# Sensors.net
KiCad netlist of a schematic drawn in Altium Designer
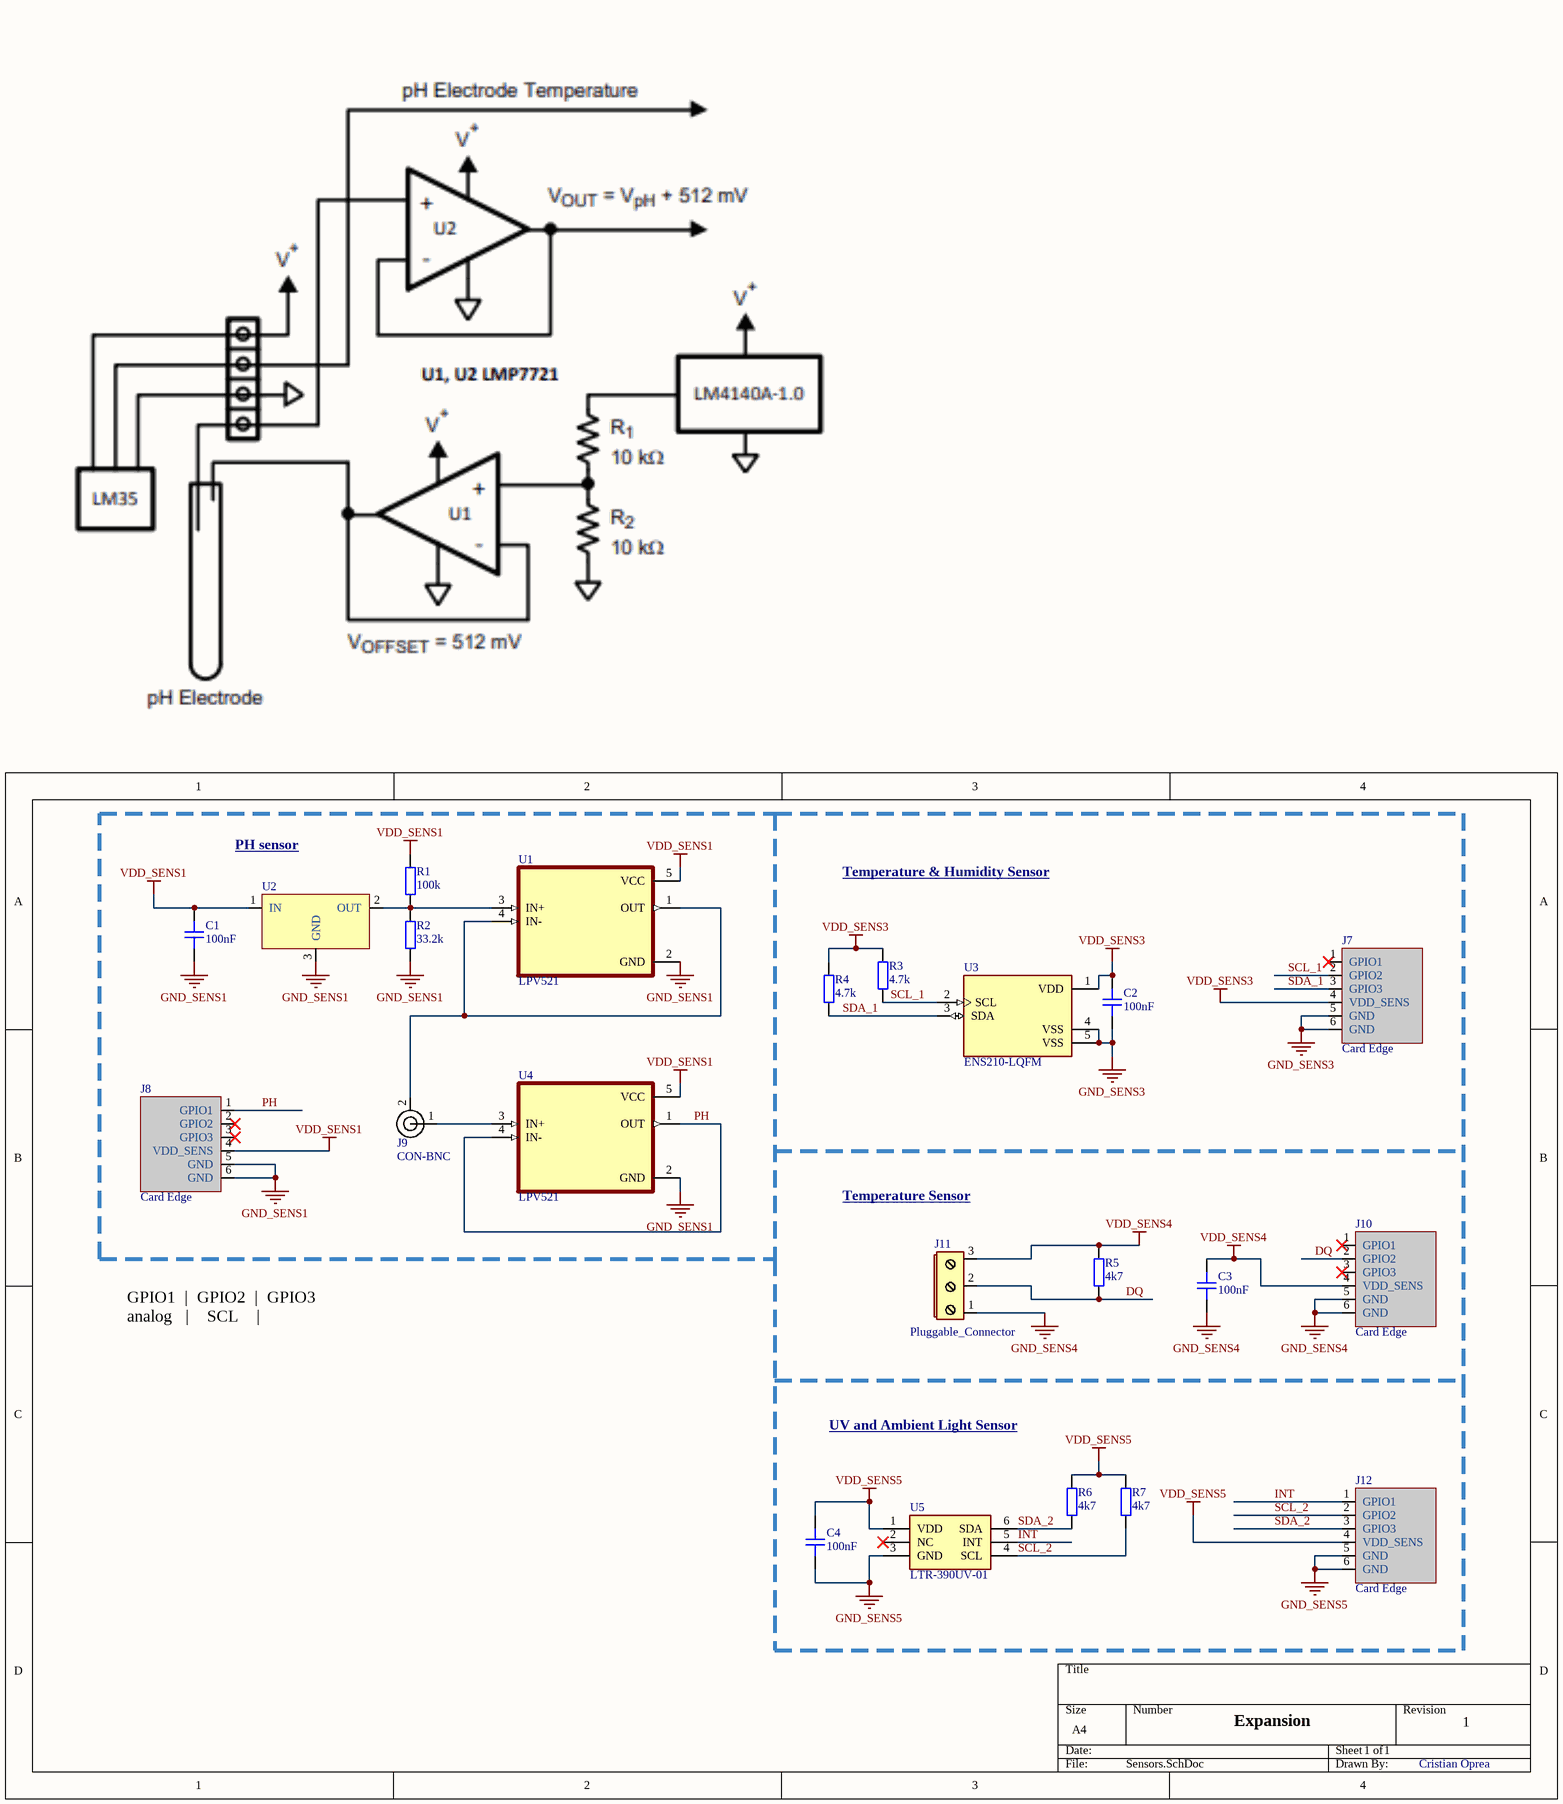
[diagram p0: Sensors.SchDoc]

(export (version "E")
  (design (tool "Eeschema 10.0.6"))
  (components
    (comp (ref "C1")
      (value "100nF")
      (footprint "C0603")
      (description "Capacitor SMD 0603")
      (libsource (lib "Schlib1") (part "CAP_0603"))
    )
    (comp (ref "C2")
      (value "100nF")
      (footprint "C0603")
      (description "Capacitor SMD 0603")
      (libsource (lib "Schlib1") (part "CAP_0603"))
    )
    (comp (ref "C3")
      (value "100nF")
      (footprint "C0603")
      (description "Capacitor SMD 0603")
      (libsource (lib "Schlib1") (part "CAP_0603"))
    )
    (comp (ref "C4")
      (value "100nF")
      (footprint "C0603")
      (description "Capacitor SMD 0603")
      (libsource (lib "Schlib1") (part "CAP_0603"))
    )
    (comp (ref "J7")
      (value "Card Edge")
      (footprint "Card Edge")
      (description "Card Edge pads for 2.54 mm pitch edge connector")
      (libsource (lib "") (part "Card Edge_1"))
    )
    (comp (ref "J8")
      (value "Card Edge")
      (footprint "Card Edge")
      (description "Card Edge pads for 2.54 mm pitch edge connector")
      (libsource (lib "Schlib1") (part "Card Edge"))
    )
    (comp (ref "J9")
      (value "CON-BNC")
      (footprint "CON_BNC_MOLEX_0731375003")
      (description "RF Connector BNC Female 50 Ohms PCB TH Mount")
      (fields
        (field (name "MANUFACTURER") "RF Solutions")
        (field (name "MANUFACTURER PART NUMBER") "CON-SMA-EDGE-S")
      )
      (libsource (lib "Schlib1") (part "CON-BNC"))
    )
    (comp (ref "J10")
      (value "Card Edge")
      (footprint "Card Edge")
      (description "Card Edge pads for 2.54 mm pitch edge connector")
      (libsource (lib "") (part "Card Edge_1"))
    )
    (comp (ref "J11")
      (value "Pluggable_Connector")
      (footprint "5mm_screw_terminal_3_pos")
      (description "Screw terminal or plug terminal")
      (libsource (lib "Schlib1") (part "Pluggable_Connector"))
    )
    (comp (ref "J12")
      (value "Card Edge")
      (footprint "Card Edge")
      (description "Card Edge pads for 2.54 mm pitch edge connector")
      (libsource (lib "") (part "Card Edge_1"))
    )
    (comp (ref "R1")
      (value "100k")
      (footprint "R0603")
      (description "Resistor SMD 0603")
      (libsource (lib "Schlib1") (part "RES_0603"))
    )
    (comp (ref "R2")
      (value "33.2k")
      (footprint "R0603")
      (description "Resistor SMD 0603")
      (libsource (lib "Schlib1") (part "RES_0603"))
    )
    (comp (ref "R3")
      (value "4.7k")
      (footprint "R0603")
      (description "Resistor SMD 0603")
      (libsource (lib "Schlib1") (part "RES_0603"))
    )
    (comp (ref "R4")
      (value "4.7k")
      (footprint "R0603")
      (description "Resistor SMD 0603")
      (libsource (lib "Schlib1") (part "RES_0603"))
    )
    (comp (ref "R5")
      (value "4k7")
      (footprint "R0603")
      (description "Resistor SMD 0805")
      (libsource (lib "Schlib1") (part "RES_0805"))
    )
    (comp (ref "R6")
      (value "4k7")
      (footprint "R0603")
      (description "Resistor SMD 0805")
      (libsource (lib "Schlib1") (part "RES_0805"))
    )
    (comp (ref "R7")
      (value "4k7")
      (footprint "R0603")
      (description "Resistor SMD 0805")
      (libsource (lib "Schlib1") (part "RES_0805"))
    )
    (comp (ref "U1")
      (value "LPV521")
      (footprint "SOT65P210X110-5N")
      (fields (field (name "MP") "MAX4466EXK"))
      (libsource (lib "Schlib1") (part "LPV521"))
    )
    (comp (ref "U2")
      (value "ADR5040BKSZ-REEL7")
      (footprint "SOT23-3")
      (description "Voltage References 2.048 Low-Cost, Micropower, Low-Dropout, High-Output-Current, SOT23")
      (fields
        (field (name "MANUFACTURER") "Maxim Integrated")
        (field (name "MANUFACTURER PART NUMBER") "MAX6101EUR+T")
      )
      (libsource (lib "Schlib1") (part "VREF"))
    )
    (comp (ref "U3")
      (value "ENS210-LQFM")
      (footprint "XDCR_ENS210-LQFM")
      (description "Humidity/Temperature Sensor Digital Serial (2-Wire, I2C) 4-Pin QFN EP T/R")
      (fields (field (name "MF") "ScioSense"))
      (libsource (lib "Schlib1") (part "ENS210-LQFM"))
    )
    (comp (ref "U4")
      (value "LPV521")
      (footprint "SOT65P210X110-5N")
      (fields (field (name "MP") "MAX4466EXK"))
      (libsource (lib "Schlib1") (part "LPV521"))
    )
    (comp (ref "U5")
      (value "LTR-390UV-01")
      (footprint "LTR390-UV")
      (description "SENSOR OPT ULTRAVIOLET 6PINS")
      (fields (field (name "MOUSER PART NUMBER") "859-LTR390UV01"))
      (libsource (lib "Schlib1") (part "LTR-390UV-01"))
    )
  )
  (nets
    (net (code "1") (name "/DQ") (class "Default")
      (node (ref "J10") (pin "2") (pinfunction "GPIO2_2") (pintype "passive"))
      (node (ref "J11") (pin "2") (pinfunction "2_2") (pintype "passive"))
      (node (ref "R5") (pin "1") (pinfunction "1_1") (pintype "passive"))
    )
    (net (code "2") (name "/INT") (class "Default")
      (node (ref "J12") (pin "1") (pinfunction "GPIO1_1") (pintype "passive"))
      (node (ref "U5") (pin "5") (pinfunction "INT_5") (pintype "passive"))
    )
    (net (code "3") (name "/PH") (class "Default")
      (node (ref "J8") (pin "1") (pinfunction "GPIO1_1") (pintype "passive"))
      (node (ref "U4") (pin "1") (pinfunction "OUT_1") (pintype "output"))
      (node (ref "U4") (pin "4") (pinfunction "IN-_4") (pintype "input"))
    )
    (net (code "4") (name "/SCL_1") (class "Default")
      (node (ref "J7") (pin "2") (pinfunction "GPIO2_2") (pintype "passive"))
      (node (ref "R3") (pin "1") (pinfunction "1_1") (pintype "passive"))
      (node (ref "U3") (pin "2") (pinfunction "SCL_2") (pintype "input"))
    )
    (net (code "5") (name "/SCL_2") (class "Default")
      (node (ref "J12") (pin "2") (pinfunction "GPIO2_2") (pintype "passive"))
      (node (ref "R7") (pin "1") (pinfunction "1_1") (pintype "passive"))
      (node (ref "U5") (pin "4") (pinfunction "SCL_4") (pintype "passive"))
    )
    (net (code "6") (name "/SDA_1") (class "Default")
      (node (ref "J7") (pin "3") (pinfunction "GPIO3_3") (pintype "passive"))
      (node (ref "R4") (pin "2") (pinfunction "2_2") (pintype "passive"))
      (node (ref "U3") (pin "3") (pinfunction "SDA_3") (pintype "bidirectional"))
    )
    (net (code "7") (name "/SDA_2") (class "Default")
      (node (ref "J12") (pin "3") (pinfunction "GPIO3_3") (pintype "passive"))
      (node (ref "R6") (pin "1") (pinfunction "1_1") (pintype "passive"))
      (node (ref "U5") (pin "6") (pinfunction "SDA_6") (pintype "passive"))
    )
    (net (code "8") (name "GND_SENS1") (class "Default")
      (node (ref "C1") (pin "1") (pinfunction "1_1") (pintype "passive"))
      (node (ref "J8") (pin "5") (pinfunction "GND_5") (pintype "passive"))
      (node (ref "J8") (pin "6") (pinfunction "GND_6") (pintype "passive"))
      (node (ref "R2") (pin "1") (pinfunction "1_1") (pintype "passive"))
      (node (ref "U1") (pin "2") (pinfunction "GND_2") (pintype "power_in"))
      (node (ref "U2") (pin "3") (pinfunction "GND_3") (pintype "passive"))
      (node (ref "U4") (pin "2") (pinfunction "GND_2") (pintype "power_in"))
    )
    (net (code "9") (name "GND_SENS3") (class "Default")
      (node (ref "C2") (pin "1") (pinfunction "1_1") (pintype "passive"))
      (node (ref "J7") (pin "5") (pinfunction "GND_5") (pintype "passive"))
      (node (ref "J7") (pin "6") (pinfunction "GND_6") (pintype "passive"))
      (node (ref "U3") (pin "4") (pinfunction "VSS_4") (pintype "power_in"))
      (node (ref "U3") (pin "5") (pinfunction "VSS_5") (pintype "power_in"))
    )
    (net (code "10") (name "GND_SENS4") (class "Default")
      (node (ref "C3") (pin "1") (pinfunction "1_1") (pintype "passive"))
      (node (ref "J10") (pin "5") (pinfunction "GND_5") (pintype "passive"))
      (node (ref "J10") (pin "6") (pinfunction "GND_6") (pintype "passive"))
      (node (ref "J11") (pin "1") (pinfunction "1_1") (pintype "passive"))
    )
    (net (code "11") (name "GND_SENS5") (class "Default")
      (node (ref "C4") (pin "1") (pinfunction "1_1") (pintype "passive"))
      (node (ref "J12") (pin "5") (pinfunction "GND_5") (pintype "passive"))
      (node (ref "J12") (pin "6") (pinfunction "GND_6") (pintype "passive"))
      (node (ref "U5") (pin "3") (pinfunction "GND_3") (pintype "passive"))
    )
    (net (code "12") (name "Net-(U1-IN+)") (class "Default")
      (node (ref "R1") (pin "1") (pinfunction "1_1") (pintype "passive"))
      (node (ref "R2") (pin "2") (pinfunction "2_2") (pintype "passive"))
      (node (ref "U1") (pin "3") (pinfunction "IN+_3") (pintype "input"))
      (node (ref "U2") (pin "2") (pinfunction "OUT_2") (pintype "passive"))
    )
    (net (code "13") (name "Net-(U1-IN-)") (class "Default")
      (node (ref "J9") (pin "2") (pinfunction "2_2") (pintype "passive"))
      (node (ref "U1") (pin "1") (pinfunction "OUT_1") (pintype "output"))
      (node (ref "U1") (pin "4") (pinfunction "IN-_4") (pintype "input"))
    )
    (net (code "14") (name "Net-(U4-IN+)") (class "Default")
      (node (ref "J9") (pin "1") (pinfunction "1_1") (pintype "passive"))
      (node (ref "U4") (pin "3") (pinfunction "IN+_3") (pintype "input"))
    )
    (net (code "15") (name "VDD_SENS1") (class "Default")
      (node (ref "C1") (pin "2") (pinfunction "2_2") (pintype "passive"))
      (node (ref "J8") (pin "4") (pinfunction "VDD_SENS_4") (pintype "passive"))
      (node (ref "R1") (pin "2") (pinfunction "2_2") (pintype "passive"))
      (node (ref "U1") (pin "5") (pinfunction "VCC_5") (pintype "power_in"))
      (node (ref "U2") (pin "1") (pinfunction "IN_1") (pintype "passive"))
      (node (ref "U4") (pin "5") (pinfunction "VCC_5") (pintype "power_in"))
    )
    (net (code "16") (name "VDD_SENS3") (class "Default")
      (node (ref "C2") (pin "2") (pinfunction "2_2") (pintype "passive"))
      (node (ref "J7") (pin "4") (pinfunction "VDD_SENS_4") (pintype "passive"))
      (node (ref "R3") (pin "2") (pinfunction "2_2") (pintype "passive"))
      (node (ref "R4") (pin "1") (pinfunction "1_1") (pintype "passive"))
      (node (ref "U3") (pin "1") (pinfunction "VDD_1") (pintype "power_in"))
    )
    (net (code "17") (name "VDD_SENS4") (class "Default")
      (node (ref "C3") (pin "2") (pinfunction "2_2") (pintype "passive"))
      (node (ref "J10") (pin "4") (pinfunction "VDD_SENS_4") (pintype "passive"))
      (node (ref "J11") (pin "3") (pinfunction "3_3") (pintype "passive"))
      (node (ref "R5") (pin "2") (pinfunction "2_2") (pintype "passive"))
    )
    (net (code "18") (name "VDD_SENS5") (class "Default")
      (node (ref "C4") (pin "2") (pinfunction "2_2") (pintype "passive"))
      (node (ref "J12") (pin "4") (pinfunction "VDD_SENS_4") (pintype "passive"))
      (node (ref "R6") (pin "2") (pinfunction "2_2") (pintype "passive"))
      (node (ref "R7") (pin "2") (pinfunction "2_2") (pintype "passive"))
      (node (ref "U5") (pin "1") (pinfunction "VDD_1") (pintype "passive"))
    )
    (net (code "19") (name "unconnected-(J7-GPIO1-Pad1)") (class "Default")
      (node (ref "J7") (pin "1") (pinfunction "GPIO1_1") (pintype "passive+no_connect"))
    )
    (net (code "20") (name "unconnected-(J8-GPIO2-Pad2)") (class "Default")
      (node (ref "J8") (pin "2") (pinfunction "GPIO2_2") (pintype "passive+no_connect"))
    )
    (net (code "21") (name "unconnected-(J8-GPIO3-Pad3)") (class "Default")
      (node (ref "J8") (pin "3") (pinfunction "GPIO3_3") (pintype "passive+no_connect"))
    )
    (net (code "22") (name "unconnected-(J10-GPIO1-Pad1)") (class "Default")
      (node (ref "J10") (pin "1") (pinfunction "GPIO1_1") (pintype "passive+no_connect"))
    )
    (net (code "23") (name "unconnected-(J10-GPIO3-Pad3)") (class "Default")
      (node (ref "J10") (pin "3") (pinfunction "GPIO3_3") (pintype "passive+no_connect"))
    )
    (net (code "24") (name "unconnected-(U5-NC-Pad2)") (class "Default")
      (node (ref "U5") (pin "2") (pinfunction "NC_2") (pintype "passive+no_connect"))
    )
  )
)
